# fabflash-mk-2_3-driver.net
KiCad netlist of a schematic drawn in EAGLE
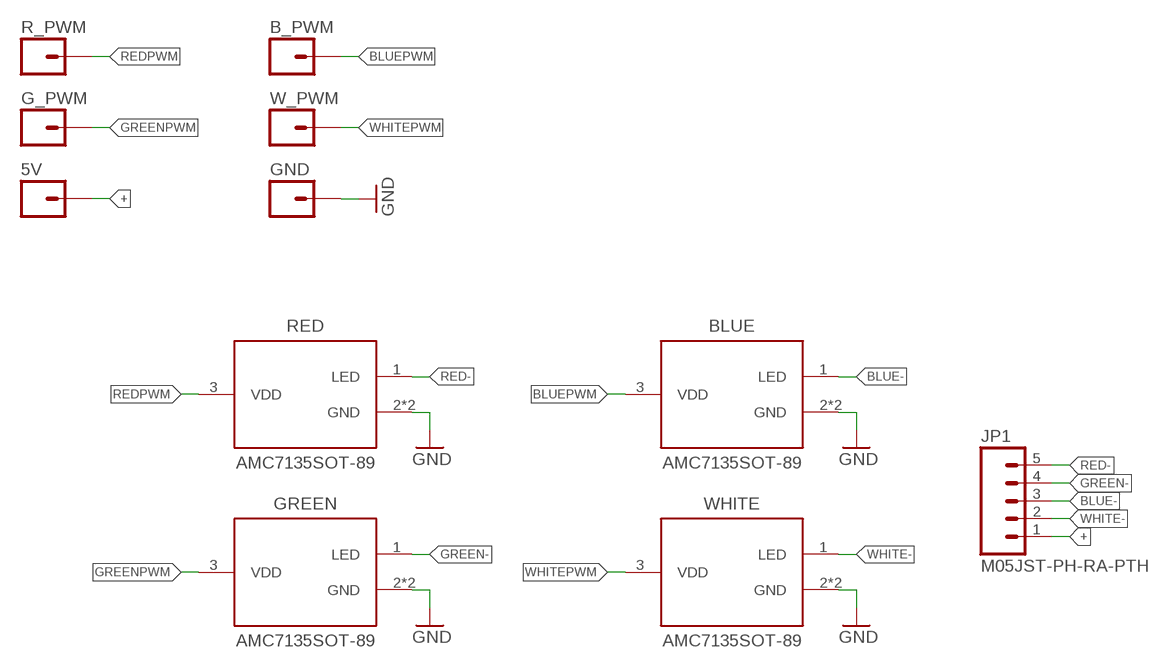
[diagram p0: schematic, sheet 1]

(export (version "E")
  (design (tool "Eeschema 10.0.6"))
  (components
    (comp (ref "5V")
      (value "M01PTH-0.9MM")
      (footprint "eagle-import:1X01-0.9MM")
      (libsource (lib "eagle-import") (part "M01PTH-0.9MM"))
    )
    (comp (ref "BLUE")
      (value "AMC7135SOT-89")
      (footprint "eagle-import:SOT89")
      (libsource (lib "eagle-import") (part "AMC7135SOT-89"))
    )
    (comp (ref "B_PWM")
      (value "M01PTH-0.9MM")
      (footprint "eagle-import:1X01-0.9MM")
      (libsource (lib "eagle-import") (part "M01PTH-0.9MM"))
    )
    (comp (ref "GND")
      (value "M01PTH-0.9MM")
      (footprint "eagle-import:1X01-0.9MM")
      (libsource (lib "eagle-import") (part "M01PTH-0.9MM"))
    )
    (comp (ref "GREEN")
      (value "AMC7135SOT-89")
      (footprint "eagle-import:SOT89")
      (libsource (lib "eagle-import") (part "AMC7135SOT-89"))
    )
    (comp (ref "G_PWM")
      (value "M01PTH-0.9MM")
      (footprint "eagle-import:1X01-0.9MM")
      (libsource (lib "eagle-import") (part "M01PTH-0.9MM"))
    )
    (comp (ref "JP1")
      (value "M05JST-PH-RA-PTH")
      (footprint "eagle-import:JST-5-PH-RA-PTH")
      (libsource (lib "eagle-import") (part "M05JST-PH-RA-PTH"))
    )
    (comp (ref "RED")
      (value "AMC7135SOT-89")
      (footprint "eagle-import:SOT89")
      (libsource (lib "eagle-import") (part "AMC7135SOT-89"))
    )
    (comp (ref "R_PWM")
      (value "M01PTH-0.9MM")
      (footprint "eagle-import:1X01-0.9MM")
      (libsource (lib "eagle-import") (part "M01PTH-0.9MM"))
    )
    (comp (ref "WHITE")
      (value "AMC7135SOT-89")
      (footprint "eagle-import:SOT89")
      (libsource (lib "eagle-import") (part "AMC7135SOT-89"))
    )
    (comp (ref "W_PWM")
      (value "M01PTH-0.9MM")
      (footprint "eagle-import:1X01-0.9MM")
      (libsource (lib "eagle-import") (part "M01PTH-0.9MM"))
    )
  )
  (nets
    (net (code "1") (name "+") (class "Default")
      (node (ref "5V") (pin "1") (pinfunction "1_1") (pintype "passive"))
      (node (ref "JP1") (pin "1") (pinfunction "1_1") (pintype "passive"))
    )
    (net (code "2") (name "BLUE-") (class "Default")
      (node (ref "BLUE") (pin "1") (pinfunction "LED_1") (pintype "bidirectional"))
      (node (ref "JP1") (pin "3") (pinfunction "3_3") (pintype "passive"))
    )
    (net (code "3") (name "BLUEPWM") (class "Default")
      (node (ref "BLUE") (pin "3") (pinfunction "VDD_3") (pintype "bidirectional"))
      (node (ref "B_PWM") (pin "1") (pinfunction "1_1") (pintype "passive"))
    )
    (net (code "4") (name "GND") (class "Default")
      (node (ref "BLUE") (pin "2") (pinfunction "GND_2") (pintype "bidirectional"))
      (node (ref "BLUE") (pin "4") (pinfunction "GND_4") (pintype "bidirectional"))
      (node (ref "GND") (pin "1") (pinfunction "1_1") (pintype "passive"))
      (node (ref "GREEN") (pin "2") (pinfunction "GND_2") (pintype "bidirectional"))
      (node (ref "GREEN") (pin "4") (pinfunction "GND_4") (pintype "bidirectional"))
      (node (ref "RED") (pin "2") (pinfunction "GND_2") (pintype "bidirectional"))
      (node (ref "RED") (pin "4") (pinfunction "GND_4") (pintype "bidirectional"))
      (node (ref "WHITE") (pin "2") (pinfunction "GND_2") (pintype "bidirectional"))
      (node (ref "WHITE") (pin "4") (pinfunction "GND_4") (pintype "bidirectional"))
    )
    (net (code "5") (name "GREEN-") (class "Default")
      (node (ref "GREEN") (pin "1") (pinfunction "LED_1") (pintype "bidirectional"))
      (node (ref "JP1") (pin "4") (pinfunction "4_4") (pintype "passive"))
    )
    (net (code "6") (name "GREENPWM") (class "Default")
      (node (ref "GREEN") (pin "3") (pinfunction "VDD_3") (pintype "bidirectional"))
      (node (ref "G_PWM") (pin "1") (pinfunction "1_1") (pintype "passive"))
    )
    (net (code "7") (name "RED-") (class "Default")
      (node (ref "JP1") (pin "5") (pinfunction "5_5") (pintype "passive"))
      (node (ref "RED") (pin "1") (pinfunction "LED_1") (pintype "bidirectional"))
    )
    (net (code "8") (name "REDPWM") (class "Default")
      (node (ref "RED") (pin "3") (pinfunction "VDD_3") (pintype "bidirectional"))
      (node (ref "R_PWM") (pin "1") (pinfunction "1_1") (pintype "passive"))
    )
    (net (code "9") (name "WHITE-") (class "Default")
      (node (ref "JP1") (pin "2") (pinfunction "2_2") (pintype "passive"))
      (node (ref "WHITE") (pin "1") (pinfunction "LED_1") (pintype "bidirectional"))
    )
    (net (code "10") (name "WHITEPWM") (class "Default")
      (node (ref "WHITE") (pin "3") (pinfunction "VDD_3") (pintype "bidirectional"))
      (node (ref "W_PWM") (pin "1") (pinfunction "1_1") (pintype "passive"))
    )
  )
)
